# Relay.net
KiCad netlist of a schematic drawn in Altium Designer
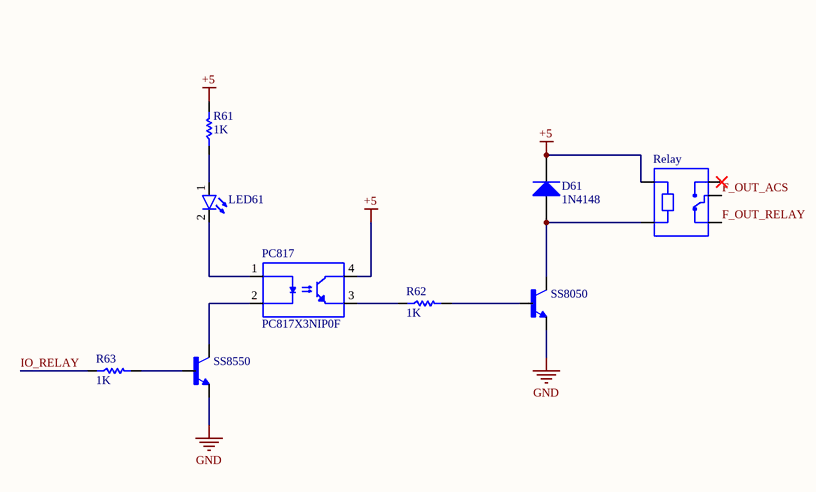
[diagram p0: Relay.SchDoc]

(export (version "E")
  (design (tool "Eeschema 10.0.6"))
  (components
    (comp (ref "D61")
      (value "1N4148")
      (footprint "LL4148")
      (description "High Conductance Fast Diode")
      (fields (field (name "PUBLISHER") "Altium Limited"))
      (libsource (lib "DDEms") (part "Diode 1N4148"))
    )
    (comp (ref "LED61")
      (value "Red")
      (footprint "LED_SMD_0805")
      (description "LED")
      (fields (field (name "DESIGNER") "Saeid Jorablo"))
      (libsource (lib "DDEms") (part "LED"))
    )
    (comp (ref "PC817")
      (value "PC817X3NIP0F")
      (footprint "SOIC254P1000X400-4N")
      (description "Optoisolator Transistor Output 5000Vrms 1 Channel 4-SMD")
      (fields (field (name "MF") "SHARP/Socle Technology"))
      (libsource (lib "PC817X3NIP0F") (part "PC817X3NIP0F"))
    )
    (comp (ref "R61")
      (value "1K")
      (footprint "SMD_RES_0805")
      (description "Resistor")
      (fields (field (name "TOLERANCE") "5%") (field (name "POWER") "1/8 W"))
      (libsource (lib "DDEms") (part "Resistor"))
    )
    (comp (ref "R62")
      (value "1K")
      (footprint "RES 0805 (2012X06L)")
      (description "Resistor")
      (fields (field (name "TOLERANCE") "5%") (field (name "POWER") "1/8 W"))
      (libsource (lib "DDEms") (part "Resistor"))
    )
    (comp (ref "R63")
      (value "1K")
      (footprint "RES 0805 (2012X06L)")
      (description "Resistor")
      (fields (field (name "TOLERANCE") "5%") (field (name "POWER") "1/8 W"))
      (libsource (lib "DDEms") (part "Resistor"))
    )
    (comp (ref "Relay")
      (value "SRD-05VDC-SL-C")
      (footprint "RELAY_SRD-05VDC-SL-C")
      (fields (field (name "MF") "Songle Relay"))
      (libsource (lib "SRD-05VDC-SL-C") (part "SRD-05VDC-SL-C"))
    )
    (comp (ref "SS8050")
      (value "BCW31*")
      (footprint "SOT23-BEC")
      (description "Bipolar _BJT_ Transistor NPN General Purpose Amplifier Surface Mount")
      (fields (field (name "MF") "ON Semiconductor") (field (name "MP") "BCW31"))
      (libsource (lib "BCW31_") (part "BCW31*"))
    )
    (comp (ref "SS8550")
      (value "BCW31*")
      (footprint "SOT23-BEC")
      (description "Bipolar _BJT_ Transistor NPN General Purpose Amplifier Surface Mount")
      (fields (field (name "MF") "ON Semiconductor") (field (name "MP") "BCW31"))
      (libsource (lib "BCW31_") (part "BCW31*"))
    )
  )
  (nets
    (net (code "1") (name "+5") (class "Default")
      (node (ref "D61") (pin "2") (pinfunction "K_2") (pintype "passive"))
      (node (ref "PC817") (pin "4") (pinfunction "COLLECTOR_4") (pintype "passive"))
      (node (ref "R61") (pin "2") (pinfunction "2_2") (pintype "passive"))
      (node (ref "Relay") (pin "A1") (pinfunction "A1_A1") (pintype "passive"))
    )
    (net (code "2") (name "/F_OUT_ACS") (class "Default")
      (node (ref "Relay") (pin "COM") (pinfunction "COM_COM") (pintype "passive"))
    )
    (net (code "3") (name "/F_OUT_RELAY") (class "Default")
      (node (ref "Relay") (pin "NC") (pinfunction "NC_NC") (pintype "passive"))
    )
    (net (code "4") (name "/IO_RELAY") (class "Default")
      (node (ref "R63") (pin "1") (pinfunction "1_1") (pintype "passive"))
    )
    (net (code "5") (name "GND") (class "Default")
      (node (ref "SS8050") (pin "E") (pinfunction "E_E") (pintype "passive"))
      (node (ref "SS8550") (pin "E") (pinfunction "E_E") (pintype "passive"))
    )
    (net (code "6") (name "Net-(D61-A)") (class "Default")
      (node (ref "D61") (pin "1") (pinfunction "A_1") (pintype "passive"))
      (node (ref "Relay") (pin "A2") (pinfunction "A2_A2") (pintype "passive"))
      (node (ref "SS8050") (pin "C") (pinfunction "C_C") (pintype "passive"))
    )
    (net (code "7") (name "Net-(LED61-A)") (class "Default")
      (node (ref "LED61") (pin "1") (pinfunction "A_1") (pintype "passive"))
      (node (ref "R61") (pin "1") (pinfunction "1_1") (pintype "passive"))
    )
    (net (code "8") (name "Net-(LED61-K)") (class "Default")
      (node (ref "LED61") (pin "2") (pinfunction "K_2") (pintype "passive"))
      (node (ref "PC817") (pin "1") (pinfunction "ANODE_1") (pintype "passive"))
    )
    (net (code "9") (name "Net-(PC817-CATHODE)") (class "Default")
      (node (ref "PC817") (pin "2") (pinfunction "CATHODE_2") (pintype "passive"))
      (node (ref "SS8550") (pin "C") (pinfunction "C_C") (pintype "passive"))
    )
    (net (code "10") (name "Net-(PC817-EMITTER)") (class "Default")
      (node (ref "PC817") (pin "3") (pinfunction "EMITTER_3") (pintype "passive"))
      (node (ref "R62") (pin "1") (pinfunction "1_1") (pintype "passive"))
    )
    (net (code "11") (name "Net-(R62-Pad2)") (class "Default")
      (node (ref "R62") (pin "2") (pinfunction "2_2") (pintype "passive"))
      (node (ref "SS8050") (pin "B") (pinfunction "B_B") (pintype "passive"))
    )
    (net (code "12") (name "Net-(R63-Pad2)") (class "Default")
      (node (ref "R63") (pin "2") (pinfunction "2_2") (pintype "passive"))
      (node (ref "SS8550") (pin "B") (pinfunction "B_B") (pintype "passive"))
    )
    (net (code "13") (name "unconnected-(Relay-PadNO)") (class "Default")
      (node (ref "Relay") (pin "NO") (pinfunction "NO_NO") (pintype "passive+no_connect"))
    )
  )
)
